# Tegra_Serial.net
KiCad netlist of a schematic drawn in Altium Designer
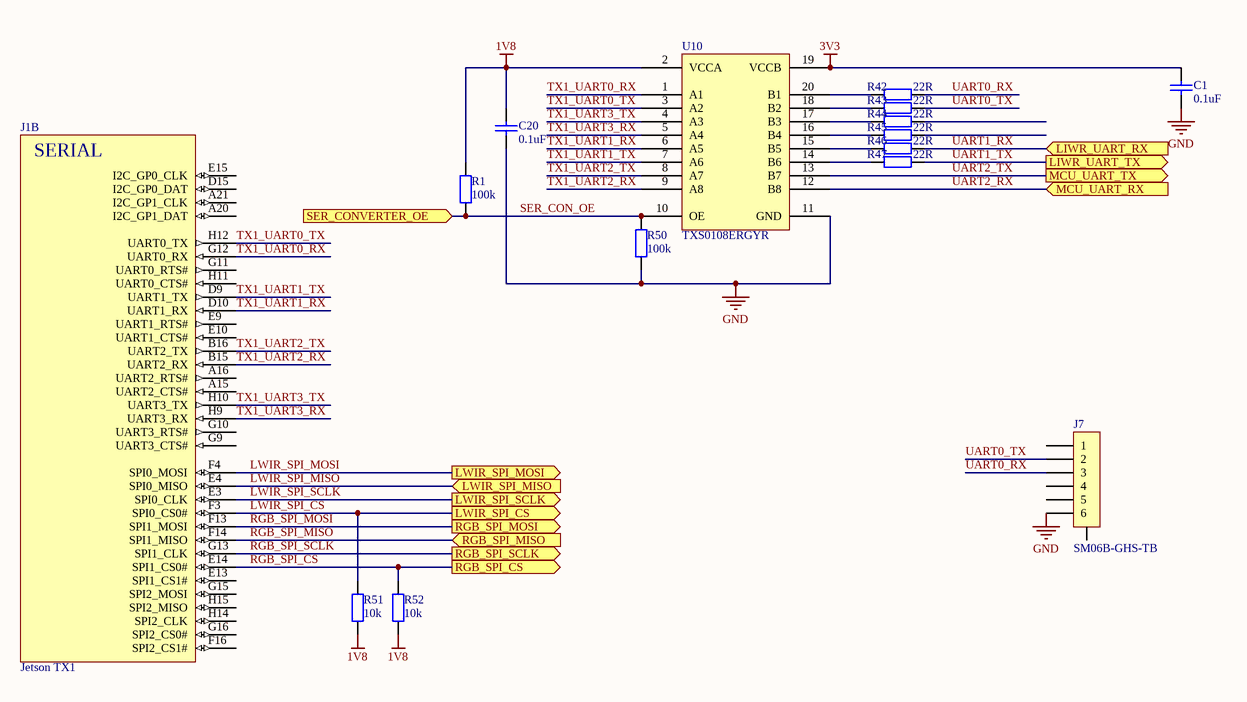
[diagram p0: Tegra_Serial.SchDoc]

(export (version "E")
  (design (tool "Eeschema 10.0.6"))
  (components
    (comp (ref "C1")
      (value "GRM155R71C104KA88D")
      (footprint "0402C_M")
      (description "CAP CER 0.1UF 16V X7R 0402")
      (fields
        (field (name "MANUFACTURER") "Murata Electronics North America")
        (field (name "TOLERANCE") "±10%")
        (field (name "CAPACITANCE") "0.1uF")
      )
      (libsource (lib "KMTI-main") (part "GRM155R71C104KA88D"))
    )
    (comp (ref "C20")
      (value "GRM155R71C104KA88D")
      (footprint "0402C_M")
      (description "CAP CER 0.1UF 16V X7R 0402")
      (fields
        (field (name "MANUFACTURER") "Murata Electronics North America")
        (field (name "TOLERANCE") "±10%")
        (field (name "CAPACITANCE") "0.1uF")
      )
      (libsource (lib "KMTI-main") (part "GRM155R71C104KA88D"))
    )
    (comp (ref "J1")
      (value "Jetson TX1")
      (footprint "Nvidia Jetson TX1")
      (description "Nvidia computing module")
      (libsource (lib "Modules") (part "NVIDIA_Jetson_TX1"))
    )
    (comp (ref "J7")
      (value "SM06B-GHS-TB")
      (footprint "SM06B-GHS-TB")
      (description "CONN HEADER GH SIDE 6POS 1.25MM")
      (fields
        (field (name "MANUFACTURER") "JST Sales America Inc.")
        (field (name "MANUFACTURER PART NUMBER") "SM06B-GHS-TB(LF)(SN)")
      )
      (libsource (lib "KMTI-main") (part "SM06B-GHS-TB(LF)(SN)"))
    )
    (comp (ref "R1")
      (value "CRCW0402100KJNED")
      (footprint "0402R_M")
      (description "RES SMD 100K OHM 5% 1/16W 0402")
      (fields
        (field (name "MANUFACTURER") "Vishay")
        (field (name "TOLERANCE") "5 %")
        (field (name "RESISTANCE") "100k")
      )
      (libsource (lib "KMTI-main") (part "CRCW0402100KJNED"))
    )
    (comp (ref "R42")
      (value "CRCW040222R0JNED")
      (footprint "0402R_M")
      (description "RES SMD 22 OHM 5% 1/16W 0402")
      (fields
        (field (name "MANUFACTURER") "Vishay / Dale")
        (field (name "TOLERANCE") "5 %")
        (field (name "RESISTANCE") "22R")
      )
      (libsource (lib "KMTI-main") (part "CRCW040222R0JNED"))
    )
    (comp (ref "R43")
      (value "CRCW040222R0JNED")
      (footprint "0402R_M")
      (description "RES SMD 22 OHM 5% 1/16W 0402")
      (fields
        (field (name "MANUFACTURER") "Vishay / Dale")
        (field (name "TOLERANCE") "5 %")
        (field (name "RESISTANCE") "22R")
      )
      (libsource (lib "KMTI-main") (part "CRCW040222R0JNED"))
    )
    (comp (ref "R44")
      (value "CRCW040222R0JNED")
      (footprint "0402R_M")
      (description "RES SMD 22 OHM 5% 1/16W 0402")
      (fields
        (field (name "MANUFACTURER") "Vishay / Dale")
        (field (name "TOLERANCE") "5 %")
        (field (name "RESISTANCE") "22R")
      )
      (libsource (lib "KMTI-main") (part "CRCW040222R0JNED"))
    )
    (comp (ref "R45")
      (value "CRCW040222R0JNED")
      (footprint "0402R_M")
      (description "RES SMD 22 OHM 5% 1/16W 0402")
      (fields
        (field (name "MANUFACTURER") "Vishay / Dale")
        (field (name "TOLERANCE") "5 %")
        (field (name "RESISTANCE") "22R")
      )
      (libsource (lib "KMTI-main") (part "CRCW040222R0JNED"))
    )
    (comp (ref "R46")
      (value "CRCW040222R0JNED")
      (footprint "0402R_M")
      (description "RES SMD 22 OHM 5% 1/16W 0402")
      (fields
        (field (name "MANUFACTURER") "Vishay / Dale")
        (field (name "TOLERANCE") "5 %")
        (field (name "RESISTANCE") "22R")
      )
      (libsource (lib "KMTI-main") (part "CRCW040222R0JNED"))
    )
    (comp (ref "R47")
      (value "CRCW040222R0JNED")
      (footprint "0402R_M")
      (description "RES SMD 22 OHM 5% 1/16W 0402")
      (fields
        (field (name "MANUFACTURER") "Vishay / Dale")
        (field (name "TOLERANCE") "5 %")
        (field (name "RESISTANCE") "22R")
      )
      (libsource (lib "KMTI-main") (part "CRCW040222R0JNED"))
    )
    (comp (ref "R50")
      (value "CRCW0402100KJNED")
      (footprint "0402R_M")
      (description "RES SMD 100K OHM 5% 1/16W 0402")
      (fields
        (field (name "MANUFACTURER") "Vishay")
        (field (name "TOLERANCE") "5 %")
        (field (name "RESISTANCE") "100k")
      )
      (libsource (lib "KMTI-main") (part "CRCW0402100KJNED"))
    )
    (comp (ref "R51")
      (value "10k")
      (footprint "0402R_M")
      (description "RES SMD 10K OHM 1% 1/16W 0402")
      (fields
        (field (name "MANUFACTURER") "Vishay Dale")
        (field (name "MANUFACTURER PART NUMBER") "CRCW040210K0FKED")
      )
      (libsource (lib "KMTI-main") (part "CRCW040210K0FKED"))
    )
    (comp (ref "R52")
      (value "10k")
      (footprint "0402R_M")
      (description "RES SMD 10K OHM 1% 1/16W 0402")
      (fields
        (field (name "MANUFACTURER") "Vishay Dale")
        (field (name "MANUFACTURER PART NUMBER") "CRCW040210K0FKED")
      )
      (libsource (lib "KMTI-main") (part "CRCW040210K0FKED"))
    )
    (comp (ref "U10")
      (value "TXS0108ERGYR")
      (footprint "VQFN20")
      (description "IC XLATR VOLT-LVL 8B BDIR 20QFN")
      (fields (field (name "MANUFACTURER") "Texas Instruments"))
      (libsource (lib "KMTI-main") (part "TXS0108ERGYR"))
    )
  )
  (nets
    (net (code "1") (name "/LWIR_SPI_CS") (class "Default")
      (node (ref "J1") (pin "F3") (pinfunction "SPI0_CS0#_F3") (pintype "bidirectional"))
      (node (ref "R51") (pin "2") (pinfunction "2_2") (pintype "passive"))
    )
    (net (code "2") (name "/LWIR_SPI_MISO") (class "Default")
      (node (ref "J1") (pin "E4") (pinfunction "SPI0_MISO_E4") (pintype "bidirectional"))
    )
    (net (code "3") (name "/LWIR_SPI_MOSI") (class "Default")
      (node (ref "J1") (pin "F4") (pinfunction "SPI0_MOSI_F4") (pintype "bidirectional"))
    )
    (net (code "4") (name "/LWIR_SPI_SCLK") (class "Default")
      (node (ref "J1") (pin "E3") (pinfunction "SPI0_CLK_E3") (pintype "bidirectional"))
    )
    (net (code "5") (name "/RGB_SPI_CS") (class "Default")
      (node (ref "J1") (pin "E14") (pinfunction "SPI1_CS0#_E14") (pintype "bidirectional"))
      (node (ref "R52") (pin "2") (pinfunction "2_2") (pintype "passive"))
    )
    (net (code "6") (name "/RGB_SPI_MISO") (class "Default")
      (node (ref "J1") (pin "F14") (pinfunction "SPI1_MISO_F14") (pintype "bidirectional"))
    )
    (net (code "7") (name "/RGB_SPI_MOSI") (class "Default")
      (node (ref "J1") (pin "F13") (pinfunction "SPI1_MOSI_F13") (pintype "bidirectional"))
    )
    (net (code "8") (name "/RGB_SPI_SCLK") (class "Default")
      (node (ref "J1") (pin "G13") (pinfunction "SPI1_CLK_G13") (pintype "bidirectional"))
    )
    (net (code "9") (name "/SER_CON_OE") (class "Default")
      (node (ref "R1") (pin "1") (pinfunction "1_1") (pintype "passive"))
      (node (ref "R50") (pin "2") (pinfunction "2_2") (pintype "passive"))
      (node (ref "U10") (pin "10") (pinfunction "OE_10") (pintype "passive"))
    )
    (net (code "10") (name "/TX1_UART0_RX") (class "Default")
      (node (ref "J1") (pin "G12") (pinfunction "UART0_RX_G12") (pintype "input"))
      (node (ref "U10") (pin "1") (pinfunction "A1_1") (pintype "passive"))
    )
    (net (code "11") (name "/TX1_UART0_TX") (class "Default")
      (node (ref "J1") (pin "H12") (pinfunction "UART0_TX_H12") (pintype "output"))
      (node (ref "U10") (pin "3") (pinfunction "A2_3") (pintype "passive"))
    )
    (net (code "12") (name "/TX1_UART1_RX") (class "Default")
      (node (ref "J1") (pin "D10") (pinfunction "UART1_RX_D10") (pintype "input"))
      (node (ref "U10") (pin "6") (pinfunction "A5_6") (pintype "passive"))
    )
    (net (code "13") (name "/TX1_UART1_TX") (class "Default")
      (node (ref "J1") (pin "D9") (pinfunction "UART1_TX_D9") (pintype "output"))
      (node (ref "U10") (pin "7") (pinfunction "A6_7") (pintype "passive"))
    )
    (net (code "14") (name "/TX1_UART2_RX") (class "Default")
      (node (ref "J1") (pin "B15") (pinfunction "UART2_RX_B15") (pintype "input"))
      (node (ref "U10") (pin "9") (pinfunction "A8_9") (pintype "passive"))
    )
    (net (code "15") (name "/TX1_UART2_TX") (class "Default")
      (node (ref "J1") (pin "B16") (pinfunction "UART2_TX_B16") (pintype "output"))
      (node (ref "U10") (pin "8") (pinfunction "A7_8") (pintype "passive"))
    )
    (net (code "16") (name "/TX1_UART3_RX") (class "Default")
      (node (ref "J1") (pin "H9") (pinfunction "UART3_RX_H9") (pintype "input"))
      (node (ref "U10") (pin "5") (pinfunction "A4_5") (pintype "passive"))
    )
    (net (code "17") (name "/TX1_UART3_TX") (class "Default")
      (node (ref "J1") (pin "H10") (pinfunction "UART3_TX_H10") (pintype "output"))
      (node (ref "U10") (pin "4") (pinfunction "A3_4") (pintype "passive"))
    )
    (net (code "18") (name "/UART0_RX") (class "Default")
      (node (ref "J7") (pin "3") (pinfunction "3_3") (pintype "passive"))
      (node (ref "R42") (pin "2") (pinfunction "2_2") (pintype "passive"))
    )
    (net (code "19") (name "/UART0_TX") (class "Default")
      (node (ref "J7") (pin "2") (pinfunction "2_2") (pintype "passive"))
      (node (ref "R43") (pin "2") (pinfunction "2_2") (pintype "passive"))
    )
    (net (code "20") (name "/UART1_RX") (class "Default")
      (node (ref "R46") (pin "2") (pinfunction "2_2") (pintype "passive"))
    )
    (net (code "21") (name "/UART1_TX") (class "Default")
      (node (ref "R47") (pin "2") (pinfunction "2_2") (pintype "passive"))
    )
    (net (code "22") (name "/UART2_RX") (class "Default")
      (node (ref "U10") (pin "12") (pinfunction "B8_12") (pintype "passive"))
    )
    (net (code "23") (name "/UART2_TX") (class "Default")
      (node (ref "U10") (pin "13") (pinfunction "B7_13") (pintype "passive"))
    )
    (net (code "24") (name "1V8") (class "Default")
      (node (ref "C20") (pin "2") (pinfunction "2_2") (pintype "passive"))
      (node (ref "R1") (pin "2") (pinfunction "2_2") (pintype "passive"))
      (node (ref "R51") (pin "1") (pinfunction "1_1") (pintype "passive"))
      (node (ref "R52") (pin "1") (pinfunction "1_1") (pintype "passive"))
      (node (ref "U10") (pin "2") (pinfunction "VCCA_2") (pintype "passive"))
    )
    (net (code "25") (name "3V3") (class "Default")
      (node (ref "C1") (pin "2") (pinfunction "2_2") (pintype "passive"))
      (node (ref "U10") (pin "19") (pinfunction "VCCB_19") (pintype "passive"))
    )
    (net (code "26") (name "GND") (class "Default")
      (node (ref "C1") (pin "1") (pinfunction "1_1") (pintype "passive"))
      (node (ref "C20") (pin "1") (pinfunction "1_1") (pintype "passive"))
      (node (ref "J7") (pin "6") (pinfunction "6_6") (pintype "passive"))
      (node (ref "R50") (pin "1") (pinfunction "1_1") (pintype "passive"))
      (node (ref "U10") (pin "11") (pinfunction "GND_11") (pintype "passive"))
    )
    (net (code "27") (name "Net-(U10-B1)") (class "Default")
      (node (ref "R42") (pin "1") (pinfunction "1_1") (pintype "passive"))
      (node (ref "U10") (pin "20") (pinfunction "B1_20") (pintype "passive"))
    )
    (net (code "28") (name "Net-(U10-B2)") (class "Default")
      (node (ref "R43") (pin "1") (pinfunction "1_1") (pintype "passive"))
      (node (ref "U10") (pin "18") (pinfunction "B2_18") (pintype "passive"))
    )
    (net (code "29") (name "Net-(U10-B3)") (class "Default")
      (node (ref "R44") (pin "1") (pinfunction "1_1") (pintype "passive"))
      (node (ref "U10") (pin "17") (pinfunction "B3_17") (pintype "passive"))
    )
    (net (code "30") (name "Net-(U10-B4)") (class "Default")
      (node (ref "R45") (pin "1") (pinfunction "1_1") (pintype "passive"))
      (node (ref "U10") (pin "16") (pinfunction "B4_16") (pintype "passive"))
    )
    (net (code "31") (name "Net-(U10-B5)") (class "Default")
      (node (ref "R46") (pin "1") (pinfunction "1_1") (pintype "passive"))
      (node (ref "U10") (pin "15") (pinfunction "B5_15") (pintype "passive"))
    )
    (net (code "32") (name "Net-(U10-B6)") (class "Default")
      (node (ref "R47") (pin "1") (pinfunction "1_1") (pintype "passive"))
      (node (ref "U10") (pin "14") (pinfunction "B6_14") (pintype "passive"))
    )
    (net (code "33") (name "unconnected-(J1B-I2C_GP0_CLK-PadE15)") (class "Default")
      (node (ref "J1") (pin "E15") (pinfunction "I2C_GP0_CLK_E15") (pintype "bidirectional"))
    )
    (net (code "34") (name "unconnected-(J1B-I2C_GP0_DAT-PadD15)") (class "Default")
      (node (ref "J1") (pin "D15") (pinfunction "I2C_GP0_DAT_D15") (pintype "bidirectional"))
    )
    (net (code "35") (name "unconnected-(J1B-I2C_GP1_CLK-PadA21)") (class "Default")
      (node (ref "J1") (pin "A21") (pinfunction "I2C_GP1_CLK_A21") (pintype "bidirectional"))
    )
    (net (code "36") (name "unconnected-(J1B-I2C_GP1_DAT-PadA20)") (class "Default")
      (node (ref "J1") (pin "A20") (pinfunction "I2C_GP1_DAT_A20") (pintype "bidirectional"))
    )
    (net (code "37") (name "unconnected-(J1B-SPI1_CS1#-PadE13)") (class "Default")
      (node (ref "J1") (pin "E13") (pinfunction "SPI1_CS1#_E13") (pintype "bidirectional"))
    )
    (net (code "38") (name "unconnected-(J1B-SPI2_CLK-PadH14)") (class "Default")
      (node (ref "J1") (pin "H14") (pinfunction "SPI2_CLK_H14") (pintype "bidirectional"))
    )
    (net (code "39") (name "unconnected-(J1B-SPI2_CS0#-PadG16)") (class "Default")
      (node (ref "J1") (pin "G16") (pinfunction "SPI2_CS0#_G16") (pintype "bidirectional"))
    )
    (net (code "40") (name "unconnected-(J1B-SPI2_CS1#-PadF16)") (class "Default")
      (node (ref "J1") (pin "F16") (pinfunction "SPI2_CS1#_F16") (pintype "bidirectional"))
    )
    (net (code "41") (name "unconnected-(J1B-SPI2_MISO-PadH15)") (class "Default")
      (node (ref "J1") (pin "H15") (pinfunction "SPI2_MISO_H15") (pintype "bidirectional"))
    )
    (net (code "42") (name "unconnected-(J1B-SPI2_MOSI-PadG15)") (class "Default")
      (node (ref "J1") (pin "G15") (pinfunction "SPI2_MOSI_G15") (pintype "bidirectional"))
    )
    (net (code "43") (name "unconnected-(J1B-UART0_CTS#-PadH11)") (class "Default")
      (node (ref "J1") (pin "H11") (pinfunction "UART0_CTS#_H11") (pintype "input"))
    )
    (net (code "44") (name "unconnected-(J1B-UART0_RTS#-PadG11)") (class "Default")
      (node (ref "J1") (pin "G11") (pinfunction "UART0_RTS#_G11") (pintype "output"))
    )
    (net (code "45") (name "unconnected-(J1B-UART1_CTS#-PadE10)") (class "Default")
      (node (ref "J1") (pin "E10") (pinfunction "UART1_CTS#_E10") (pintype "input"))
    )
    (net (code "46") (name "unconnected-(J1B-UART1_RTS#-PadE9)") (class "Default")
      (node (ref "J1") (pin "E9") (pinfunction "UART1_RTS#_E9") (pintype "output"))
    )
    (net (code "47") (name "unconnected-(J1B-UART2_CTS#-PadA15)") (class "Default")
      (node (ref "J1") (pin "A15") (pinfunction "UART2_CTS#_A15") (pintype "input"))
    )
    (net (code "48") (name "unconnected-(J1B-UART2_RTS#-PadA16)") (class "Default")
      (node (ref "J1") (pin "A16") (pinfunction "UART2_RTS#_A16") (pintype "output"))
    )
    (net (code "49") (name "unconnected-(J1B-UART3_CTS#-PadG9)") (class "Default")
      (node (ref "J1") (pin "G9") (pinfunction "UART3_CTS#_G9") (pintype "input"))
    )
    (net (code "50") (name "unconnected-(J1B-UART3_RTS#-PadG10)") (class "Default")
      (node (ref "J1") (pin "G10") (pinfunction "UART3_RTS#_G10") (pintype "output"))
    )
    (net (code "51") (name "unconnected-(J7-Pad0)") (class "Default")
      (node (ref "J7") (pin "0") (pinfunction "0_0") (pintype "passive"))
    )
    (net (code "52") (name "unconnected-(J7-Pad1)") (class "Default")
      (node (ref "J7") (pin "1") (pinfunction "1_1") (pintype "passive"))
    )
    (net (code "53") (name "unconnected-(J7-Pad4)") (class "Default")
      (node (ref "J7") (pin "4") (pinfunction "4_4") (pintype "passive"))
    )
    (net (code "54") (name "unconnected-(J7-Pad5)") (class "Default")
      (node (ref "J7") (pin "5") (pinfunction "5_5") (pintype "passive"))
    )
    (net (code "55") (name "unconnected-(R44-Pad2)") (class "Default")
      (node (ref "R44") (pin "2") (pinfunction "2_2") (pintype "passive"))
    )
    (net (code "56") (name "unconnected-(R45-Pad2)") (class "Default")
      (node (ref "R45") (pin "2") (pinfunction "2_2") (pintype "passive"))
    )
  )
)
